# S2C_IOs3V3_SelectSPI.net
KiCad netlist of a schematic drawn in Altium Designer
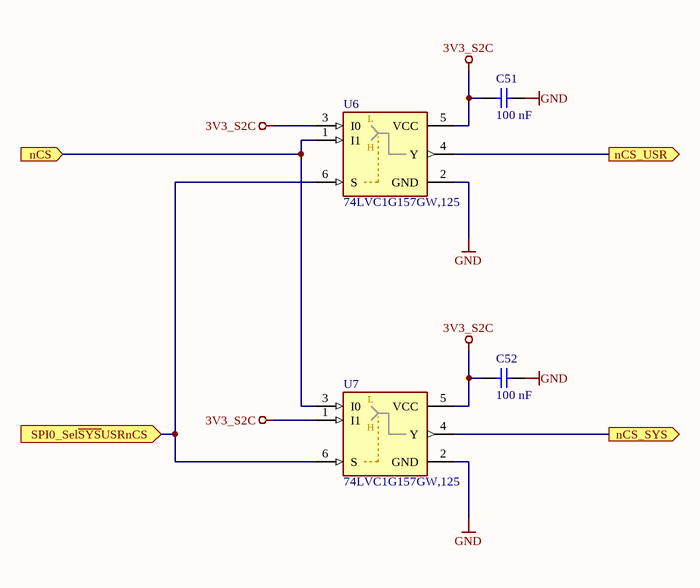
[diagram p0: S2C_IOs3V3_SelectSPI.SchDoc]

(export (version "E")
  (design (tool "Eeschema 10.0.6"))
  (components
    (comp (ref "C51")
      (value "100 nF")
      (footprint "C_0603_TE")
      (description "Generic capacitor")
      (fields
        (field (name "MANUFACTURER PART NUMBER") "UZgen_C_0603_100nF_50V_X7R")
        (field (name "MANUFACTURER") "UZgen")
        (field (name "CREATED FROM") "AGeiger")
      )
      (libsource (lib "user") (part "CAP-NP"))
    )
    (comp (ref "C52")
      (value "100 nF")
      (footprint "C_0603_TE")
      (description "Generic capacitor")
      (fields
        (field (name "MANUFACTURER PART NUMBER") "UZgen_C_0603_100nF_50V_X7R")
        (field (name "MANUFACTURER") "UZgen")
        (field (name "CREATED FROM") "AGeiger")
      )
      (libsource (lib "user") (part "CAP-NP"))
    )
    (comp (ref "U6")
      (value "74LVC1G157GW,125")
      (footprint "SOT-363")
      (description "Single 2-input multiplexer")
      (fields
        (field (name "MANUFACTURER") "Nexperia")
        (field (name "LCSC PART NUMBER") "C135822")
        (field (name "CREATED FROM") "MGeier")
      )
      (libsource (lib "user") (part "74LVC1G157"))
    )
    (comp (ref "U7")
      (value "74LVC1G157GW,125")
      (footprint "SOT-363")
      (description "Single 2-input multiplexer")
      (fields
        (field (name "MANUFACTURER") "Nexperia")
        (field (name "LCSC PART NUMBER") "C135822")
        (field (name "CREATED FROM") "MGeier")
      )
      (libsource (lib "user") (part "74LVC1G157"))
    )
  )
  (nets
    (net (code "1") (name "/SPI0_Sel~{SYS}USRnCS") (class "Default")
      (node (ref "U6") (pin "6") (pinfunction "S_6") (pintype "input"))
      (node (ref "U7") (pin "6") (pinfunction "S_6") (pintype "input"))
    )
    (net (code "2") (name "/nCS") (class "Default")
      (node (ref "U6") (pin "1") (pinfunction "I1_1") (pintype "input"))
      (node (ref "U7") (pin "3") (pinfunction "I0_3") (pintype "input"))
    )
    (net (code "3") (name "/nCS_SYS") (class "Default")
      (node (ref "U7") (pin "4") (pinfunction "Y_4") (pintype "output"))
    )
    (net (code "4") (name "/nCS_USR") (class "Default")
      (node (ref "U6") (pin "4") (pinfunction "Y_4") (pintype "output"))
    )
    (net (code "5") (name "3V3_S2C") (class "Default")
      (node (ref "C51") (pin "2") (pinfunction "2_2") (pintype "passive"))
      (node (ref "C52") (pin "2") (pinfunction "2_2") (pintype "passive"))
      (node (ref "U6") (pin "3") (pinfunction "I0_3") (pintype "input"))
      (node (ref "U6") (pin "5") (pinfunction "VCC_5") (pintype "power_in"))
      (node (ref "U7") (pin "1") (pinfunction "I1_1") (pintype "input"))
      (node (ref "U7") (pin "5") (pinfunction "VCC_5") (pintype "power_in"))
    )
    (net (code "6") (name "GND") (class "Default")
      (node (ref "C51") (pin "1") (pinfunction "1_1") (pintype "passive"))
      (node (ref "C52") (pin "1") (pinfunction "1_1") (pintype "passive"))
      (node (ref "U6") (pin "2") (pinfunction "GND_2") (pintype "power_in"))
      (node (ref "U7") (pin "2") (pinfunction "GND_2") (pintype "power_in"))
    )
  )
)
